# Control_amp.net
KiCad netlist of a schematic drawn in EAGLE
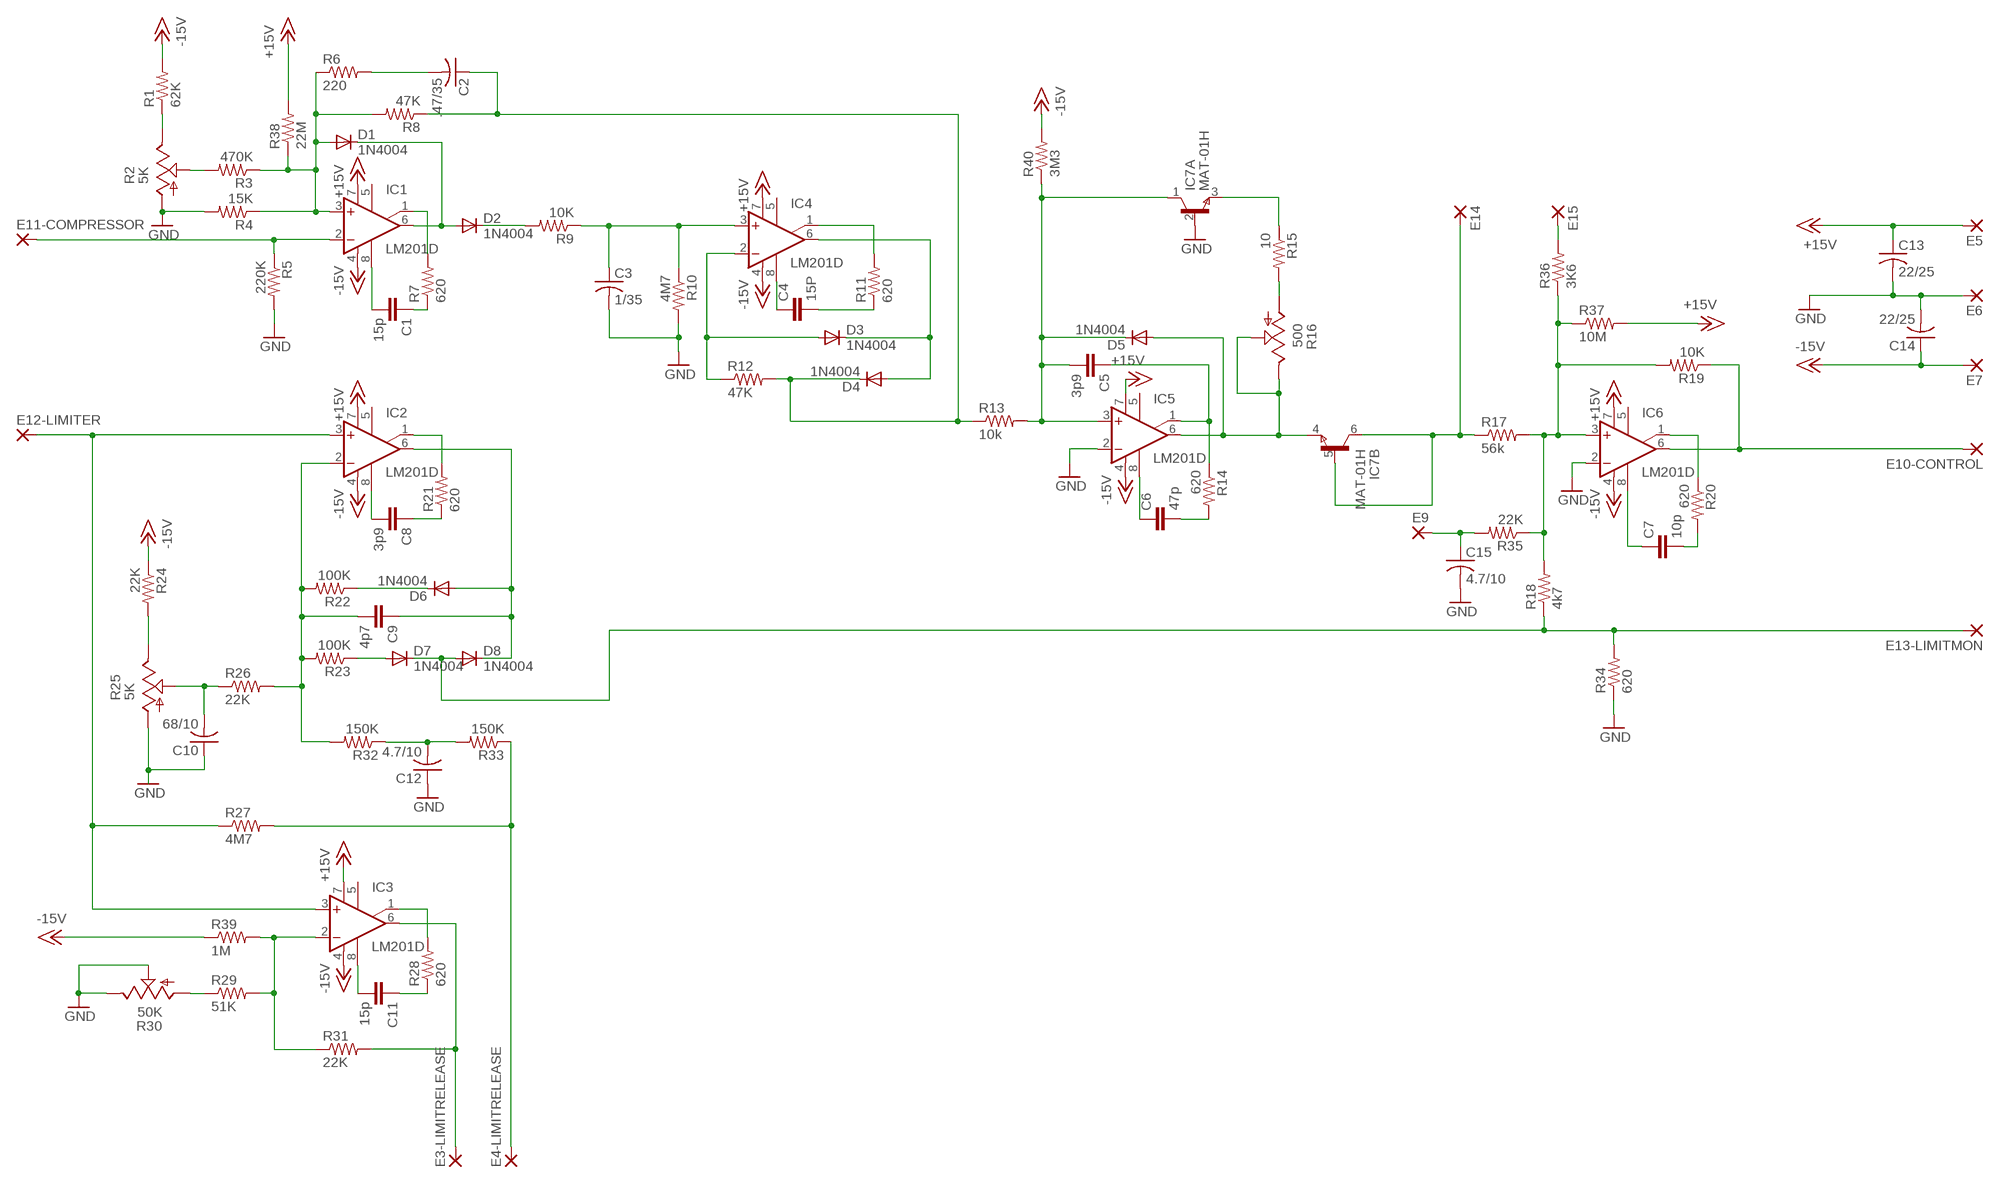
[diagram p0: schematic, sheet 1]

(export (version "E")
  (design (tool "Eeschema 10.0.6"))
  (components
    (comp (ref "C1")
      (value "15p")
      (footprint "eagle-import:C2.5-5")
      (libsource (lib "eagle-import") (part "C2.5/5"))
    )
    (comp (ref "C2")
      (value ".47/35")
      (footprint "eagle-import:C0805")
      (libsource (lib "eagle-import") (part "C-USC0805"))
    )
    (comp (ref "C3")
      (value "1/35")
      (footprint "eagle-import:C0805")
      (libsource (lib "eagle-import") (part "C-USC0805"))
    )
    (comp (ref "C4")
      (value "15P")
      (footprint "eagle-import:C2.5-5")
      (libsource (lib "eagle-import") (part "C2.5/5"))
    )
    (comp (ref "C5")
      (value "3p9")
      (footprint "eagle-import:C2.5-5")
      (libsource (lib "eagle-import") (part "C2.5/5"))
    )
    (comp (ref "C6")
      (value "47p")
      (footprint "eagle-import:C2.5-5")
      (libsource (lib "eagle-import") (part "C2.5/5"))
    )
    (comp (ref "C7")
      (value "10p")
      (footprint "eagle-import:C2.5-5")
      (libsource (lib "eagle-import") (part "C2.5/5"))
    )
    (comp (ref "C8")
      (value "3p9")
      (footprint "eagle-import:C2.5-5")
      (libsource (lib "eagle-import") (part "C2.5/5"))
    )
    (comp (ref "C9")
      (value "4p7")
      (footprint "eagle-import:C2.5-5")
      (libsource (lib "eagle-import") (part "C2.5/5"))
    )
    (comp (ref "C10")
      (value "68/10")
      (footprint "eagle-import:C0805")
      (libsource (lib "eagle-import") (part "C-USC0805"))
    )
    (comp (ref "C11")
      (value "15p")
      (footprint "eagle-import:C2.5-5")
      (libsource (lib "eagle-import") (part "C2.5/5"))
    )
    (comp (ref "C12")
      (value "4.7/10")
      (footprint "eagle-import:C0805")
      (libsource (lib "eagle-import") (part "C-USC0805"))
    )
    (comp (ref "C13")
      (value "22/25")
      (footprint "eagle-import:C0805")
      (libsource (lib "eagle-import") (part "C-USC0805"))
    )
    (comp (ref "C14")
      (value "22/25")
      (footprint "eagle-import:C0805")
      (libsource (lib "eagle-import") (part "C-USC0805"))
    )
    (comp (ref "C15")
      (value "4.7/10")
      (footprint "eagle-import:C0805")
      (libsource (lib "eagle-import") (part "C-USC0805"))
    )
    (comp (ref "D1")
      (value "1N4004")
      (footprint "eagle-import:DO41-10")
      (libsource (lib "eagle-import") (part "1N4004"))
    )
    (comp (ref "D2")
      (value "1N4004")
      (footprint "eagle-import:DO41-10")
      (libsource (lib "eagle-import") (part "1N4004"))
    )
    (comp (ref "D3")
      (value "1N4004")
      (footprint "eagle-import:DO41-10")
      (libsource (lib "eagle-import") (part "1N4004"))
    )
    (comp (ref "D4")
      (value "1N4004")
      (footprint "eagle-import:DO41-10")
      (libsource (lib "eagle-import") (part "1N4004"))
    )
    (comp (ref "D5")
      (value "1N4004")
      (footprint "eagle-import:DO41-10")
      (libsource (lib "eagle-import") (part "1N4004"))
    )
    (comp (ref "D6")
      (value "1N4004")
      (footprint "eagle-import:DO41-10")
      (libsource (lib "eagle-import") (part "1N4004"))
    )
    (comp (ref "D7")
      (value "1N4004")
      (footprint "eagle-import:DO41-10")
      (libsource (lib "eagle-import") (part "1N4004"))
    )
    (comp (ref "D8")
      (value "1N4004")
      (footprint "eagle-import:DO41-10")
      (libsource (lib "eagle-import") (part "1N4004"))
    )
    (comp (ref "E3-LIMITRELEASE")
      (value "SMD2")
      (footprint "eagle-import:SMD1,27-2,54")
      (libsource (lib "eagle-import") (part "SMD2"))
    )
    (comp (ref "E4-LIMITRELEASE")
      (value "SMD2")
      (footprint "eagle-import:SMD1,27-2,54")
      (libsource (lib "eagle-import") (part "SMD2"))
    )
    (comp (ref "E5")
      (value "SMD2")
      (footprint "eagle-import:SMD1,27-2,54")
      (libsource (lib "eagle-import") (part "SMD2"))
    )
    (comp (ref "E6")
      (value "SMD2")
      (footprint "eagle-import:SMD1,27-2,54")
      (libsource (lib "eagle-import") (part "SMD2"))
    )
    (comp (ref "E7")
      (value "SMD2")
      (footprint "eagle-import:SMD1,27-2,54")
      (libsource (lib "eagle-import") (part "SMD2"))
    )
    (comp (ref "E9")
      (value "SMD2")
      (footprint "eagle-import:SMD1,27-2,54")
      (libsource (lib "eagle-import") (part "SMD2"))
    )
    (comp (ref "E10-CONTROL")
      (value "SMD2")
      (footprint "eagle-import:SMD1,27-2,54")
      (libsource (lib "eagle-import") (part "SMD2"))
    )
    (comp (ref "E11-COMPRESSOR")
      (value "SMD2")
      (footprint "eagle-import:SMD1,27-2,54")
      (libsource (lib "eagle-import") (part "SMD2"))
    )
    (comp (ref "E12-LIMITER")
      (value "SMD2")
      (footprint "eagle-import:SMD1,27-2,54")
      (libsource (lib "eagle-import") (part "SMD2"))
    )
    (comp (ref "E13-LIMITMON")
      (value "SMD2")
      (footprint "eagle-import:SMD1,27-2,54")
      (libsource (lib "eagle-import") (part "SMD2"))
    )
    (comp (ref "E14")
      (value "SMD2")
      (footprint "eagle-import:SMD1,27-2,54")
      (libsource (lib "eagle-import") (part "SMD2"))
    )
    (comp (ref "E15")
      (value "SMD2")
      (footprint "eagle-import:SMD1,27-2,54")
      (libsource (lib "eagle-import") (part "SMD2"))
    )
    (comp (ref "IC1")
      (value "LM201D")
      (footprint "eagle-import:SO08")
      (libsource (lib "eagle-import") (part "LM201D"))
    )
    (comp (ref "IC2")
      (value "LM201D")
      (footprint "eagle-import:SO08")
      (libsource (lib "eagle-import") (part "LM201D"))
    )
    (comp (ref "IC3")
      (value "LM201D")
      (footprint "eagle-import:SO08")
      (libsource (lib "eagle-import") (part "LM201D"))
    )
    (comp (ref "IC4")
      (value "LM201D")
      (footprint "eagle-import:SO08")
      (libsource (lib "eagle-import") (part "LM201D"))
    )
    (comp (ref "IC5")
      (value "LM201D")
      (footprint "eagle-import:SO08")
      (libsource (lib "eagle-import") (part "LM201D"))
    )
    (comp (ref "IC6")
      (value "LM201D")
      (footprint "eagle-import:SO08")
      (libsource (lib "eagle-import") (part "LM201D"))
    )
    (comp (ref "IC7")
      (value "MAT-01H")
      (footprint "eagle-import:TO78")
      (libsource (lib "eagle-import") (part "MAT-01H"))
    )
    (comp (ref "R1")
      (value "62K")
      (footprint "eagle-import:R0805")
      (libsource (lib "eagle-import") (part "R-US_R0805"))
    )
    (comp (ref "R2")
      (value "5K")
      (footprint "eagle-import:3223G")
      (libsource (lib "eagle-import") (part "TRIM_US-3223G"))
    )
    (comp (ref "R3")
      (value "470K")
      (footprint "eagle-import:R0805")
      (libsource (lib "eagle-import") (part "R-US_R0805"))
    )
    (comp (ref "R4")
      (value "15K")
      (footprint "eagle-import:R0805")
      (libsource (lib "eagle-import") (part "R-US_R0805"))
    )
    (comp (ref "R5")
      (value "220K")
      (footprint "eagle-import:R0805")
      (libsource (lib "eagle-import") (part "R-US_R0805"))
    )
    (comp (ref "R6")
      (value "220")
      (footprint "eagle-import:R0805")
      (libsource (lib "eagle-import") (part "R-US_R0805"))
    )
    (comp (ref "R7")
      (value "620")
      (footprint "eagle-import:R0805")
      (libsource (lib "eagle-import") (part "R-US_R0805"))
    )
    (comp (ref "R8")
      (value "47K")
      (footprint "eagle-import:R0805")
      (libsource (lib "eagle-import") (part "R-US_R0805"))
    )
    (comp (ref "R9")
      (value "10K")
      (footprint "eagle-import:R0805")
      (libsource (lib "eagle-import") (part "R-US_R0805"))
    )
    (comp (ref "R10")
      (value "4M7")
      (footprint "eagle-import:R0805")
      (libsource (lib "eagle-import") (part "R-US_R0805"))
    )
    (comp (ref "R11")
      (value "620")
      (footprint "eagle-import:R0805")
      (libsource (lib "eagle-import") (part "R-US_R0805"))
    )
    (comp (ref "R12")
      (value "47K")
      (footprint "eagle-import:R0805")
      (libsource (lib "eagle-import") (part "R-US_R0805"))
    )
    (comp (ref "R13")
      (value "10k")
      (footprint "eagle-import:R0805")
      (libsource (lib "eagle-import") (part "R-US_R0805"))
    )
    (comp (ref "R14")
      (value "620")
      (footprint "eagle-import:R0805")
      (libsource (lib "eagle-import") (part "R-US_R0805"))
    )
    (comp (ref "R15")
      (value "10")
      (footprint "eagle-import:R0805")
      (libsource (lib "eagle-import") (part "R-US_R0805"))
    )
    (comp (ref "R16")
      (value "500")
      (footprint "eagle-import:3223G")
      (libsource (lib "eagle-import") (part "TRIM_US-3223G"))
    )
    (comp (ref "R17")
      (value "56k")
      (footprint "eagle-import:R0805")
      (libsource (lib "eagle-import") (part "R-US_R0805"))
    )
    (comp (ref "R18")
      (value "4k7")
      (footprint "eagle-import:R0805")
      (libsource (lib "eagle-import") (part "R-US_R0805"))
    )
    (comp (ref "R19")
      (value "10K")
      (footprint "eagle-import:R0805")
      (libsource (lib "eagle-import") (part "R-US_R0805"))
    )
    (comp (ref "R20")
      (value "620")
      (footprint "eagle-import:R0805")
      (libsource (lib "eagle-import") (part "R-US_R0805"))
    )
    (comp (ref "R21")
      (value "620")
      (footprint "eagle-import:R0805")
      (libsource (lib "eagle-import") (part "R-US_R0805"))
    )
    (comp (ref "R22")
      (value "100K")
      (footprint "eagle-import:R0805")
      (libsource (lib "eagle-import") (part "R-US_R0805"))
    )
    (comp (ref "R23")
      (value "100K")
      (footprint "eagle-import:R0805")
      (libsource (lib "eagle-import") (part "R-US_R0805"))
    )
    (comp (ref "R24")
      (value "22K")
      (footprint "eagle-import:R0805")
      (libsource (lib "eagle-import") (part "R-US_R0805"))
    )
    (comp (ref "R25")
      (value "5K")
      (footprint "eagle-import:3223G")
      (libsource (lib "eagle-import") (part "TRIM_US-3223G"))
    )
    (comp (ref "R26")
      (value "22K")
      (footprint "eagle-import:R0805")
      (libsource (lib "eagle-import") (part "R-US_R0805"))
    )
    (comp (ref "R27")
      (value "4M7")
      (footprint "eagle-import:R0805")
      (libsource (lib "eagle-import") (part "R-US_R0805"))
    )
    (comp (ref "R28")
      (value "620")
      (footprint "eagle-import:R0805")
      (libsource (lib "eagle-import") (part "R-US_R0805"))
    )
    (comp (ref "R29")
      (value "51K")
      (footprint "eagle-import:R0805")
      (libsource (lib "eagle-import") (part "R-US_R0805"))
    )
    (comp (ref "R30")
      (value "50K")
      (footprint "eagle-import:3223G")
      (libsource (lib "eagle-import") (part "TRIM_US-3223G"))
    )
    (comp (ref "R31")
      (value "22K")
      (footprint "eagle-import:R0805")
      (libsource (lib "eagle-import") (part "R-US_R0805"))
    )
    (comp (ref "R32")
      (value "150K")
      (footprint "eagle-import:R0805")
      (libsource (lib "eagle-import") (part "R-US_R0805"))
    )
    (comp (ref "R33")
      (value "150K")
      (footprint "eagle-import:R0805")
      (libsource (lib "eagle-import") (part "R-US_R0805"))
    )
    (comp (ref "R34")
      (value "620")
      (footprint "eagle-import:R0805")
      (libsource (lib "eagle-import") (part "R-US_R0805"))
    )
    (comp (ref "R35")
      (value "22K")
      (footprint "eagle-import:R0805")
      (libsource (lib "eagle-import") (part "R-US_R0805"))
    )
    (comp (ref "R36")
      (value "3K6")
      (footprint "eagle-import:R0805")
      (libsource (lib "eagle-import") (part "R-US_R0805"))
    )
    (comp (ref "R37")
      (value "10M")
      (footprint "eagle-import:R0805")
      (libsource (lib "eagle-import") (part "R-US_R0805"))
    )
    (comp (ref "R38")
      (value "22M")
      (footprint "eagle-import:R0805")
      (libsource (lib "eagle-import") (part "R-US_R0805"))
    )
    (comp (ref "R39")
      (value "1M")
      (footprint "eagle-import:R0805")
      (libsource (lib "eagle-import") (part "R-US_R0805"))
    )
    (comp (ref "R40")
      (value "3M3")
      (footprint "eagle-import:R0805")
      (libsource (lib "eagle-import") (part "R-US_R0805"))
    )
  )
  (nets
    (net (code "1") (name "+15V") (class "Default")
      (node (ref "C13") (pin "1") (pinfunction "1_1") (pintype "passive"))
      (node (ref "E5") (pin "1") (pinfunction "P_1") (pintype "passive"))
      (node (ref "IC1") (pin "7") (pinfunction "V+_7") (pintype "power_in"))
      (node (ref "IC2") (pin "7") (pinfunction "V+_7") (pintype "power_in"))
      (node (ref "IC3") (pin "7") (pinfunction "V+_7") (pintype "power_in"))
      (node (ref "IC4") (pin "7") (pinfunction "V+_7") (pintype "power_in"))
      (node (ref "IC5") (pin "7") (pinfunction "V+_7") (pintype "power_in"))
      (node (ref "IC6") (pin "7") (pinfunction "V+_7") (pintype "power_in"))
      (node (ref "R37") (pin "2") (pinfunction "2_2") (pintype "passive"))
      (node (ref "R38") (pin "2") (pinfunction "2_2") (pintype "passive"))
    )
    (net (code "2") (name "-15V") (class "Default")
      (node (ref "C14") (pin "1") (pinfunction "1_1") (pintype "passive"))
      (node (ref "E7") (pin "1") (pinfunction "P_1") (pintype "passive"))
      (node (ref "IC1") (pin "4") (pinfunction "V-_4") (pintype "power_in"))
      (node (ref "IC2") (pin "4") (pinfunction "V-_4") (pintype "power_in"))
      (node (ref "IC3") (pin "4") (pinfunction "V-_4") (pintype "power_in"))
      (node (ref "IC4") (pin "4") (pinfunction "V-_4") (pintype "power_in"))
      (node (ref "IC5") (pin "4") (pinfunction "V-_4") (pintype "power_in"))
      (node (ref "IC6") (pin "4") (pinfunction "V-_4") (pintype "power_in"))
      (node (ref "R1") (pin "2") (pinfunction "2_2") (pintype "passive"))
      (node (ref "R24") (pin "1") (pinfunction "1_1") (pintype "passive"))
      (node (ref "R39") (pin "1") (pinfunction "1_1") (pintype "passive"))
      (node (ref "R40") (pin "2") (pinfunction "2_2") (pintype "passive"))
    )
    (net (code "3") (name "GND") (class "Default")
      (node (ref "C10") (pin "1") (pinfunction "1_1") (pintype "passive"))
      (node (ref "C12") (pin "1") (pinfunction "1_1") (pintype "passive"))
      (node (ref "C13") (pin "2") (pinfunction "2_2") (pintype "passive"))
      (node (ref "C14") (pin "2") (pinfunction "2_2") (pintype "passive"))
      (node (ref "C15") (pin "2") (pinfunction "2_2") (pintype "passive"))
      (node (ref "C3") (pin "2") (pinfunction "2_2") (pintype "passive"))
      (node (ref "E6") (pin "1") (pinfunction "P_1") (pintype "passive"))
      (node (ref "IC5") (pin "2") (pinfunction "-IN_2") (pintype "input"))
      (node (ref "IC6") (pin "2") (pinfunction "-IN_2") (pintype "input"))
      (node (ref "IC7") (pin "2") (pinfunction "B_2") (pintype "passive"))
      (node (ref "R10") (pin "2") (pinfunction "2_2") (pintype "passive"))
      (node (ref "R2") (pin "1") (pinfunction "A_1") (pintype "passive"))
      (node (ref "R25") (pin "1") (pinfunction "A_1") (pintype "passive"))
      (node (ref "R30") (pin "2") (pinfunction "S_2") (pintype "passive"))
      (node (ref "R30") (pin "3") (pinfunction "E_3") (pintype "passive"))
      (node (ref "R34") (pin "1") (pinfunction "1_1") (pintype "passive"))
      (node (ref "R4") (pin "2") (pinfunction "2_2") (pintype "passive"))
      (node (ref "R5") (pin "2") (pinfunction "2_2") (pintype "passive"))
    )
    (net (code "4") (name "Net-(C1-Pad1)") (class "Default")
      (node (ref "C1") (pin "1") (pinfunction "1_1") (pintype "passive"))
      (node (ref "R7") (pin "1") (pinfunction "1_1") (pintype "passive"))
    )
    (net (code "5") (name "Net-(C2-Pad1)") (class "Default")
      (node (ref "C2") (pin "1") (pinfunction "1_1") (pintype "passive"))
      (node (ref "D4") (pin "C") (pinfunction "C_C") (pintype "passive"))
      (node (ref "R12") (pin "2") (pinfunction "2_2") (pintype "passive"))
      (node (ref "R13") (pin "1") (pinfunction "1_1") (pintype "passive"))
      (node (ref "R8") (pin "1") (pinfunction "1_1") (pintype "passive"))
    )
    (net (code "6") (name "Net-(C2-Pad2)") (class "Default")
      (node (ref "C2") (pin "2") (pinfunction "2_2") (pintype "passive"))
      (node (ref "R6") (pin "2") (pinfunction "2_2") (pintype "passive"))
    )
    (net (code "7") (name "Net-(C4-Pad2)") (class "Default")
      (node (ref "C4") (pin "2") (pinfunction "2_2") (pintype "passive"))
      (node (ref "R11") (pin "1") (pinfunction "1_1") (pintype "passive"))
    )
    (net (code "8") (name "Net-(C6-Pad2)") (class "Default")
      (node (ref "C6") (pin "2") (pinfunction "2_2") (pintype "passive"))
      (node (ref "R14") (pin "2") (pinfunction "2_2") (pintype "passive"))
    )
    (net (code "9") (name "Net-(C7-Pad2)") (class "Default")
      (node (ref "C7") (pin "2") (pinfunction "2_2") (pintype "passive"))
      (node (ref "R20") (pin "2") (pinfunction "2_2") (pintype "passive"))
    )
    (net (code "10") (name "Net-(C8-Pad1)") (class "Default")
      (node (ref "C8") (pin "1") (pinfunction "1_1") (pintype "passive"))
      (node (ref "R21") (pin "1") (pinfunction "1_1") (pintype "passive"))
    )
    (net (code "11") (name "Net-(C11-Pad1)") (class "Default")
      (node (ref "C11") (pin "1") (pinfunction "1_1") (pintype "passive"))
      (node (ref "R28") (pin "1") (pinfunction "1_1") (pintype "passive"))
    )
    (net (code "12") (name "Net-(C12-Pad2)") (class "Default")
      (node (ref "C12") (pin "2") (pinfunction "2_2") (pintype "passive"))
      (node (ref "R32") (pin "1") (pinfunction "1_1") (pintype "passive"))
      (node (ref "R33") (pin "2") (pinfunction "2_2") (pintype "passive"))
    )
    (net (code "13") (name "Net-(D2-PadC)") (class "Default")
      (node (ref "D2") (pin "C") (pinfunction "C_C") (pintype "passive"))
      (node (ref "R9") (pin "2") (pinfunction "2_2") (pintype "passive"))
    )
    (net (code "14") (name "Net-(D6-PadC)") (class "Default")
      (node (ref "D6") (pin "C") (pinfunction "C_C") (pintype "passive"))
      (node (ref "R22") (pin "1") (pinfunction "1_1") (pintype "passive"))
    )
    (net (code "15") (name "Net-(D7-PadA)") (class "Default")
      (node (ref "D7") (pin "A") (pinfunction "A_A") (pintype "passive"))
      (node (ref "R23") (pin "1") (pinfunction "1_1") (pintype "passive"))
    )
    (net (code "16") (name "Net-(E3-LIMITRELEASE-P)") (class "Default")
      (node (ref "E3-LIMITRELEASE") (pin "1") (pinfunction "P_1") (pintype "passive"))
      (node (ref "IC3") (pin "6") (pinfunction "OUT_6") (pintype "output"))
      (node (ref "R31") (pin "2") (pinfunction "2_2") (pintype "passive"))
    )
    (net (code "17") (name "Net-(E4-LIMITRELEASE-P)") (class "Default")
      (node (ref "E4-LIMITRELEASE") (pin "1") (pinfunction "P_1") (pintype "passive"))
      (node (ref "R27") (pin "2") (pinfunction "2_2") (pintype "passive"))
      (node (ref "R33") (pin "1") (pinfunction "1_1") (pintype "passive"))
    )
    (net (code "18") (name "Net-(E9-P)") (class "Default")
      (node (ref "C15") (pin "1") (pinfunction "1_1") (pintype "passive"))
      (node (ref "E9") (pin "1") (pinfunction "P_1") (pintype "passive"))
      (node (ref "R35") (pin "2") (pinfunction "2_2") (pintype "passive"))
    )
    (net (code "19") (name "Net-(E10-CONTROL-P)") (class "Default")
      (node (ref "E10-CONTROL") (pin "1") (pinfunction "P_1") (pintype "passive"))
      (node (ref "IC6") (pin "6") (pinfunction "OUT_6") (pintype "output"))
      (node (ref "R19") (pin "1") (pinfunction "1_1") (pintype "passive"))
    )
    (net (code "20") (name "Net-(E11-COMPRESSOR-P)") (class "Default")
      (node (ref "E11-COMPRESSOR") (pin "1") (pinfunction "P_1") (pintype "passive"))
      (node (ref "IC1") (pin "2") (pinfunction "-IN_2") (pintype "input"))
      (node (ref "R5") (pin "1") (pinfunction "1_1") (pintype "passive"))
    )
    (net (code "21") (name "Net-(E12-LIMITER-P)") (class "Default")
      (node (ref "E12-LIMITER") (pin "1") (pinfunction "P_1") (pintype "passive"))
      (node (ref "IC2") (pin "3") (pinfunction "+IN_3") (pintype "input"))
      (node (ref "IC3") (pin "3") (pinfunction "+IN_3") (pintype "input"))
      (node (ref "R27") (pin "1") (pinfunction "1_1") (pintype "passive"))
    )
    (net (code "22") (name "Net-(E13-LIMITMON-P)") (class "Default")
      (node (ref "D7") (pin "C") (pinfunction "C_C") (pintype "passive"))
      (node (ref "D8") (pin "A") (pinfunction "A_A") (pintype "passive"))
      (node (ref "E13-LIMITMON") (pin "1") (pinfunction "P_1") (pintype "passive"))
      (node (ref "R18") (pin "1") (pinfunction "1_1") (pintype "passive"))
      (node (ref "R34") (pin "2") (pinfunction "2_2") (pintype "passive"))
    )
    (net (code "23") (name "Net-(E14-P)") (class "Default")
      (node (ref "E14") (pin "1") (pinfunction "P_1") (pintype "passive"))
      (node (ref "IC7") (pin "5") (pinfunction "B_5") (pintype "passive"))
      (node (ref "IC7") (pin "6") (pinfunction "C_6") (pintype "passive"))
      (node (ref "R17") (pin "1") (pinfunction "1_1") (pintype "passive"))
    )
    (net (code "24") (name "Net-(E15-P)") (class "Default")
      (node (ref "E15") (pin "1") (pinfunction "P_1") (pintype "passive"))
      (node (ref "R36") (pin "2") (pinfunction "2_2") (pintype "passive"))
    )
    (net (code "25") (name "Net-(IC1-+IN)") (class "Default")
      (node (ref "D1") (pin "A") (pinfunction "A_A") (pintype "passive"))
      (node (ref "IC1") (pin "3") (pinfunction "+IN_3") (pintype "input"))
      (node (ref "R3") (pin "1") (pinfunction "1_1") (pintype "passive"))
      (node (ref "R38") (pin "1") (pinfunction "1_1") (pintype "passive"))
      (node (ref "R4") (pin "1") (pinfunction "1_1") (pintype "passive"))
      (node (ref "R6") (pin "1") (pinfunction "1_1") (pintype "passive"))
      (node (ref "R8") (pin "2") (pinfunction "2_2") (pintype "passive"))
    )
    (net (code "26") (name "Net-(IC1-CMP)") (class "Default")
      (node (ref "C1") (pin "2") (pinfunction "2_2") (pintype "passive"))
      (node (ref "IC1") (pin "8") (pinfunction "CMP_8") (pintype "passive"))
    )
    (net (code "27") (name "Net-(IC1-ON{slash}CMP)") (class "Default")
      (node (ref "IC1") (pin "1") (pinfunction "ON/CMP_1") (pintype "passive"))
      (node (ref "R7") (pin "2") (pinfunction "2_2") (pintype "passive"))
    )
    (net (code "28") (name "Net-(IC1-OUT)") (class "Default")
      (node (ref "D1") (pin "C") (pinfunction "C_C") (pintype "passive"))
      (node (ref "D2") (pin "A") (pinfunction "A_A") (pintype "passive"))
      (node (ref "IC1") (pin "6") (pinfunction "OUT_6") (pintype "output"))
    )
    (net (code "29") (name "Net-(IC2--IN)") (class "Default")
      (node (ref "C9") (pin "2") (pinfunction "2_2") (pintype "passive"))
      (node (ref "IC2") (pin "2") (pinfunction "-IN_2") (pintype "input"))
      (node (ref "R22") (pin "2") (pinfunction "2_2") (pintype "passive"))
      (node (ref "R23") (pin "2") (pinfunction "2_2") (pintype "passive"))
      (node (ref "R26") (pin "2") (pinfunction "2_2") (pintype "passive"))
      (node (ref "R32") (pin "2") (pinfunction "2_2") (pintype "passive"))
    )
    (net (code "30") (name "Net-(IC2-CMP)") (class "Default")
      (node (ref "C8") (pin "2") (pinfunction "2_2") (pintype "passive"))
      (node (ref "IC2") (pin "8") (pinfunction "CMP_8") (pintype "passive"))
    )
    (net (code "31") (name "Net-(IC2-ON{slash}CMP)") (class "Default")
      (node (ref "IC2") (pin "1") (pinfunction "ON/CMP_1") (pintype "passive"))
      (node (ref "R21") (pin "2") (pinfunction "2_2") (pintype "passive"))
    )
    (net (code "32") (name "Net-(IC2-OUT)") (class "Default")
      (node (ref "C9") (pin "1") (pinfunction "1_1") (pintype "passive"))
      (node (ref "D6") (pin "A") (pinfunction "A_A") (pintype "passive"))
      (node (ref "D8") (pin "C") (pinfunction "C_C") (pintype "passive"))
      (node (ref "IC2") (pin "6") (pinfunction "OUT_6") (pintype "output"))
    )
    (net (code "33") (name "Net-(IC3--IN)") (class "Default")
      (node (ref "IC3") (pin "2") (pinfunction "-IN_2") (pintype "input"))
      (node (ref "R29") (pin "2") (pinfunction "2_2") (pintype "passive"))
      (node (ref "R31") (pin "1") (pinfunction "1_1") (pintype "passive"))
      (node (ref "R39") (pin "2") (pinfunction "2_2") (pintype "passive"))
    )
    (net (code "34") (name "Net-(IC3-CMP)") (class "Default")
      (node (ref "C11") (pin "2") (pinfunction "2_2") (pintype "passive"))
      (node (ref "IC3") (pin "8") (pinfunction "CMP_8") (pintype "passive"))
    )
    (net (code "35") (name "Net-(IC3-ON{slash}CMP)") (class "Default")
      (node (ref "IC3") (pin "1") (pinfunction "ON/CMP_1") (pintype "passive"))
      (node (ref "R28") (pin "2") (pinfunction "2_2") (pintype "passive"))
    )
    (net (code "36") (name "Net-(IC4-+IN)") (class "Default")
      (node (ref "C3") (pin "1") (pinfunction "1_1") (pintype "passive"))
      (node (ref "IC4") (pin "3") (pinfunction "+IN_3") (pintype "input"))
      (node (ref "R10") (pin "1") (pinfunction "1_1") (pintype "passive"))
      (node (ref "R9") (pin "1") (pinfunction "1_1") (pintype "passive"))
    )
    (net (code "37") (name "Net-(IC4--IN)") (class "Default")
      (node (ref "D3") (pin "A") (pinfunction "A_A") (pintype "passive"))
      (node (ref "IC4") (pin "2") (pinfunction "-IN_2") (pintype "input"))
      (node (ref "R12") (pin "1") (pinfunction "1_1") (pintype "passive"))
    )
    (net (code "38") (name "Net-(IC4-CMP)") (class "Default")
      (node (ref "C4") (pin "1") (pinfunction "1_1") (pintype "passive"))
      (node (ref "IC4") (pin "8") (pinfunction "CMP_8") (pintype "passive"))
    )
    (net (code "39") (name "Net-(IC4-ON{slash}CMP)") (class "Default")
      (node (ref "IC4") (pin "1") (pinfunction "ON/CMP_1") (pintype "passive"))
      (node (ref "R11") (pin "2") (pinfunction "2_2") (pintype "passive"))
    )
    (net (code "40") (name "Net-(IC4-OUT)") (class "Default")
      (node (ref "D3") (pin "C") (pinfunction "C_C") (pintype "passive"))
      (node (ref "D4") (pin "A") (pinfunction "A_A") (pintype "passive"))
      (node (ref "IC4") (pin "6") (pinfunction "OUT_6") (pintype "output"))
    )
    (net (code "41") (name "Net-(IC5-+IN)") (class "Default")
      (node (ref "C5") (pin "2") (pinfunction "2_2") (pintype "passive"))
      (node (ref "D5") (pin "C") (pinfunction "C_C") (pintype "passive"))
      (node (ref "IC5") (pin "3") (pinfunction "+IN_3") (pintype "input"))
      (node (ref "IC7") (pin "1") (pinfunction "C_1") (pintype "passive"))
      (node (ref "R13") (pin "2") (pinfunction "2_2") (pintype "passive"))
      (node (ref "R40") (pin "1") (pinfunction "1_1") (pintype "passive"))
    )
    (net (code "42") (name "Net-(IC5-CMP)") (class "Default")
      (node (ref "C6") (pin "1") (pinfunction "1_1") (pintype "passive"))
      (node (ref "IC5") (pin "8") (pinfunction "CMP_8") (pintype "passive"))
    )
    (net (code "43") (name "Net-(IC5-ON{slash}CMP)") (class "Default")
      (node (ref "C5") (pin "1") (pinfunction "1_1") (pintype "passive"))
      (node (ref "IC5") (pin "1") (pinfunction "ON/CMP_1") (pintype "passive"))
      (node (ref "R14") (pin "1") (pinfunction "1_1") (pintype "passive"))
    )
    (net (code "44") (name "Net-(IC5-OUT)") (class "Default")
      (node (ref "D5") (pin "A") (pinfunction "A_A") (pintype "passive"))
      (node (ref "IC5") (pin "6") (pinfunction "OUT_6") (pintype "output"))
      (node (ref "IC7") (pin "4") (pinfunction "E_4") (pintype "passive"))
      (node (ref "R16") (pin "2") (pinfunction "S_2") (pintype "passive"))
      (node (ref "R16") (pin "3") (pinfunction "E_3") (pintype "passive"))
    )
    (net (code "45") (name "Net-(IC6-+IN)") (class "Default")
      (node (ref "IC6") (pin "3") (pinfunction "+IN_3") (pintype "input"))
      (node (ref "R17") (pin "2") (pinfunction "2_2") (pintype "passive"))
      (node (ref "R18") (pin "2") (pinfunction "2_2") (pintype "passive"))
      (node (ref "R19") (pin "2") (pinfunction "2_2") (pintype "passive"))
      (node (ref "R35") (pin "1") (pinfunction "1_1") (pintype "passive"))
      (node (ref "R36") (pin "1") (pinfunction "1_1") (pintype "passive"))
      (node (ref "R37") (pin "1") (pinfunction "1_1") (pintype "passive"))
    )
    (net (code "46") (name "Net-(IC6-CMP)") (class "Default")
      (node (ref "C7") (pin "1") (pinfunction "1_1") (pintype "passive"))
      (node (ref "IC6") (pin "8") (pinfunction "CMP_8") (pintype "passive"))
    )
    (net (code "47") (name "Net-(IC6-ON{slash}CMP)") (class "Default")
      (node (ref "IC6") (pin "1") (pinfunction "ON/CMP_1") (pintype "passive"))
      (node (ref "R20") (pin "1") (pinfunction "1_1") (pintype "passive"))
    )
    (net (code "48") (name "Net-(IC7A-E)") (class "Default")
      (node (ref "IC7") (pin "3") (pinfunction "E_3") (pintype "passive"))
      (node (ref "R15") (pin "1") (pinfunction "1_1") (pintype "passive"))
    )
    (net (code "49") (name "Net-(R2-E)") (class "Default")
      (node (ref "R1") (pin "1") (pinfunction "1_1") (pintype "passive"))
      (node (ref "R2") (pin "3") (pinfunction "E_3") (pintype "passive"))
    )
    (net (code "50") (name "Net-(R2-S)") (class "Default")
      (node (ref "R2") (pin "2") (pinfunction "S_2") (pintype "passive"))
      (node (ref "R3") (pin "2") (pinfunction "2_2") (pintype "passive"))
    )
    (net (code "51") (name "Net-(R16-A)") (class "Default")
      (node (ref "R15") (pin "2") (pinfunction "2_2") (pintype "passive"))
      (node (ref "R16") (pin "1") (pinfunction "A_1") (pintype "passive"))
    )
    (net (code "52") (name "Net-(R25-E)") (class "Default")
      (node (ref "R24") (pin "2") (pinfunction "2_2") (pintype "passive"))
      (node (ref "R25") (pin "3") (pinfunction "E_3") (pintype "passive"))
    )
    (net (code "53") (name "Net-(R25-S)") (class "Default")
      (node (ref "C10") (pin "2") (pinfunction "2_2") (pintype "passive"))
      (node (ref "R25") (pin "2") (pinfunction "S_2") (pintype "passive"))
      (node (ref "R26") (pin "1") (pinfunction "1_1") (pintype "passive"))
    )
    (net (code "54") (name "Net-(R30-A)") (class "Default")
      (node (ref "R29") (pin "1") (pinfunction "1_1") (pintype "passive"))
      (node (ref "R30") (pin "1") (pinfunction "A_1") (pintype "passive"))
    )
    (net (code "55") (name "unconnected-(IC1-ON-Pad5)") (class "Default")
      (node (ref "IC1") (pin "5") (pinfunction "ON_5") (pintype "passive"))
    )
    (net (code "56") (name "unconnected-(IC2-ON-Pad5)") (class "Default")
      (node (ref "IC2") (pin "5") (pinfunction "ON_5") (pintype "passive"))
    )
    (net (code "57") (name "unconnected-(IC3-ON-Pad5)") (class "Default")
      (node (ref "IC3") (pin "5") (pinfunction "ON_5") (pintype "passive"))
    )
    (net (code "58") (name "unconnected-(IC4-ON-Pad5)") (class "Default")
      (node (ref "IC4") (pin "5") (pinfunction "ON_5") (pintype "passive"))
    )
    (net (code "59") (name "unconnected-(IC5-ON-Pad5)") (class "Default")
      (node (ref "IC5") (pin "5") (pinfunction "ON_5") (pintype "passive"))
    )
    (net (code "60") (name "unconnected-(IC6-ON-Pad5)") (class "Default")
      (node (ref "IC6") (pin "5") (pinfunction "ON_5") (pintype "passive"))
    )
  )
)
